# WhatCompressor.net
KiCad netlist of a schematic drawn in EAGLE
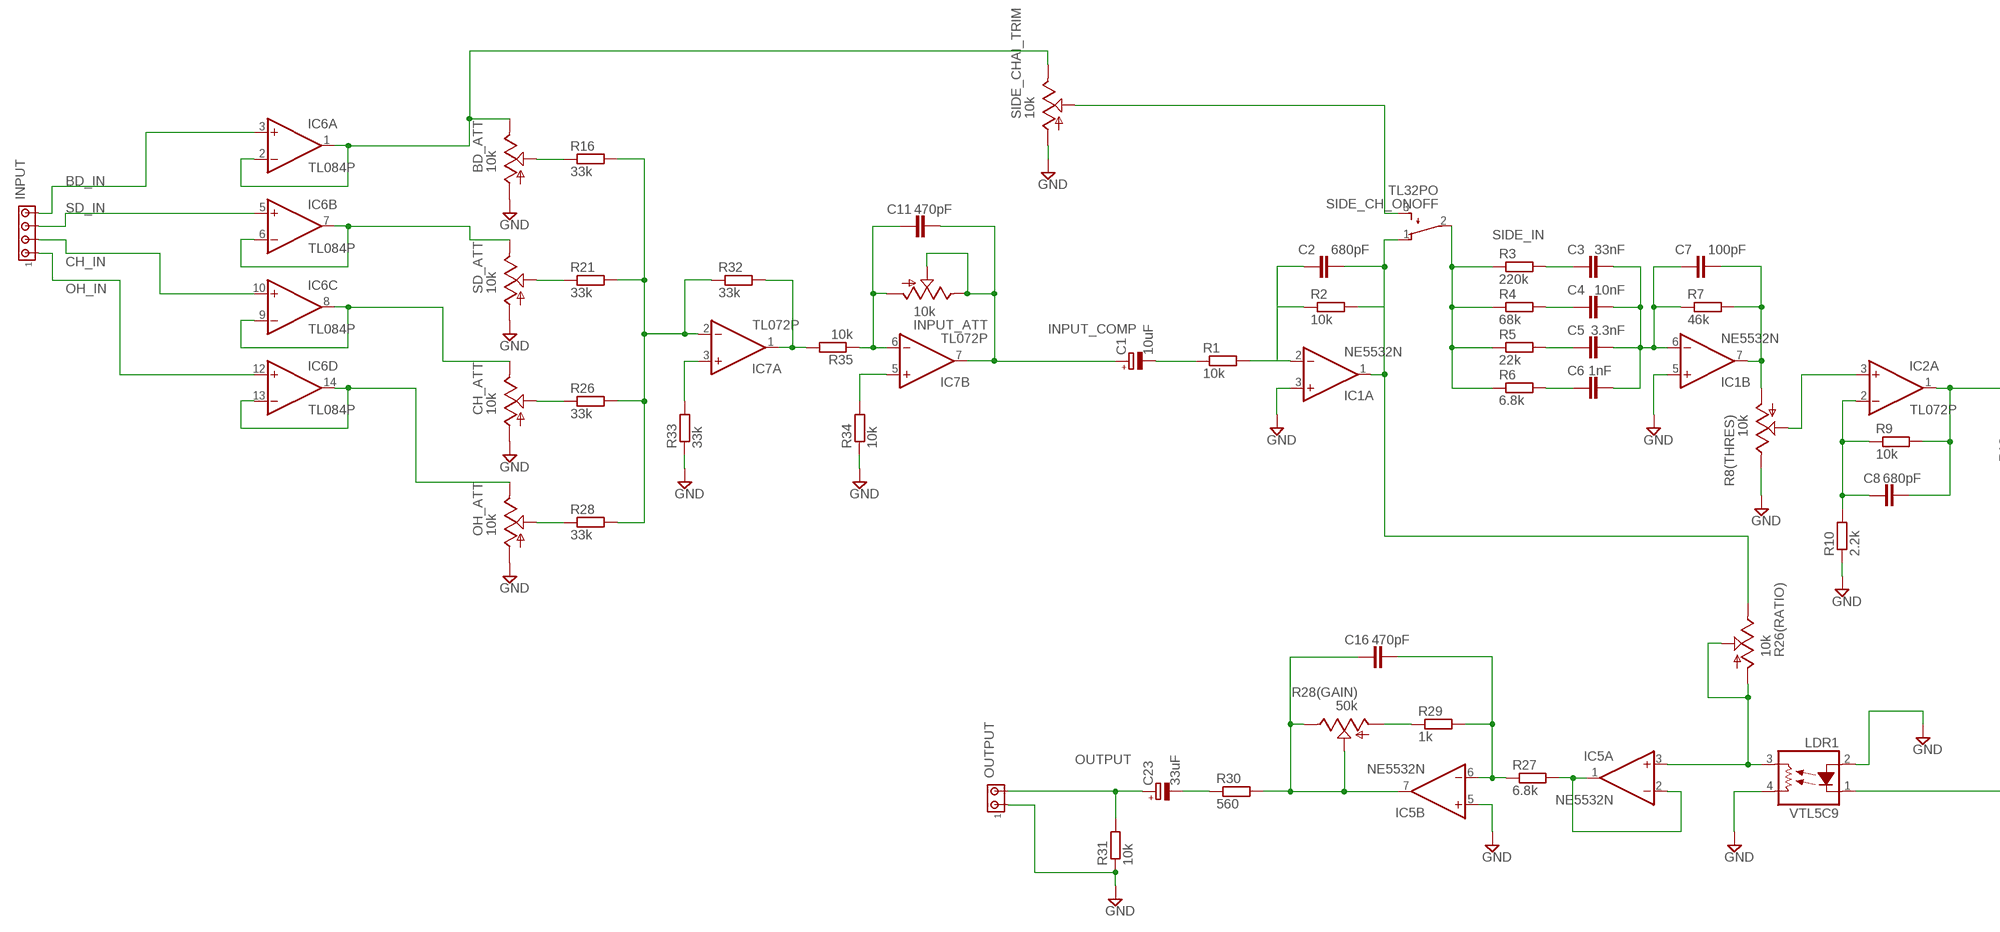
[diagram p0: schematic, sheet 1, part 1 of 2]
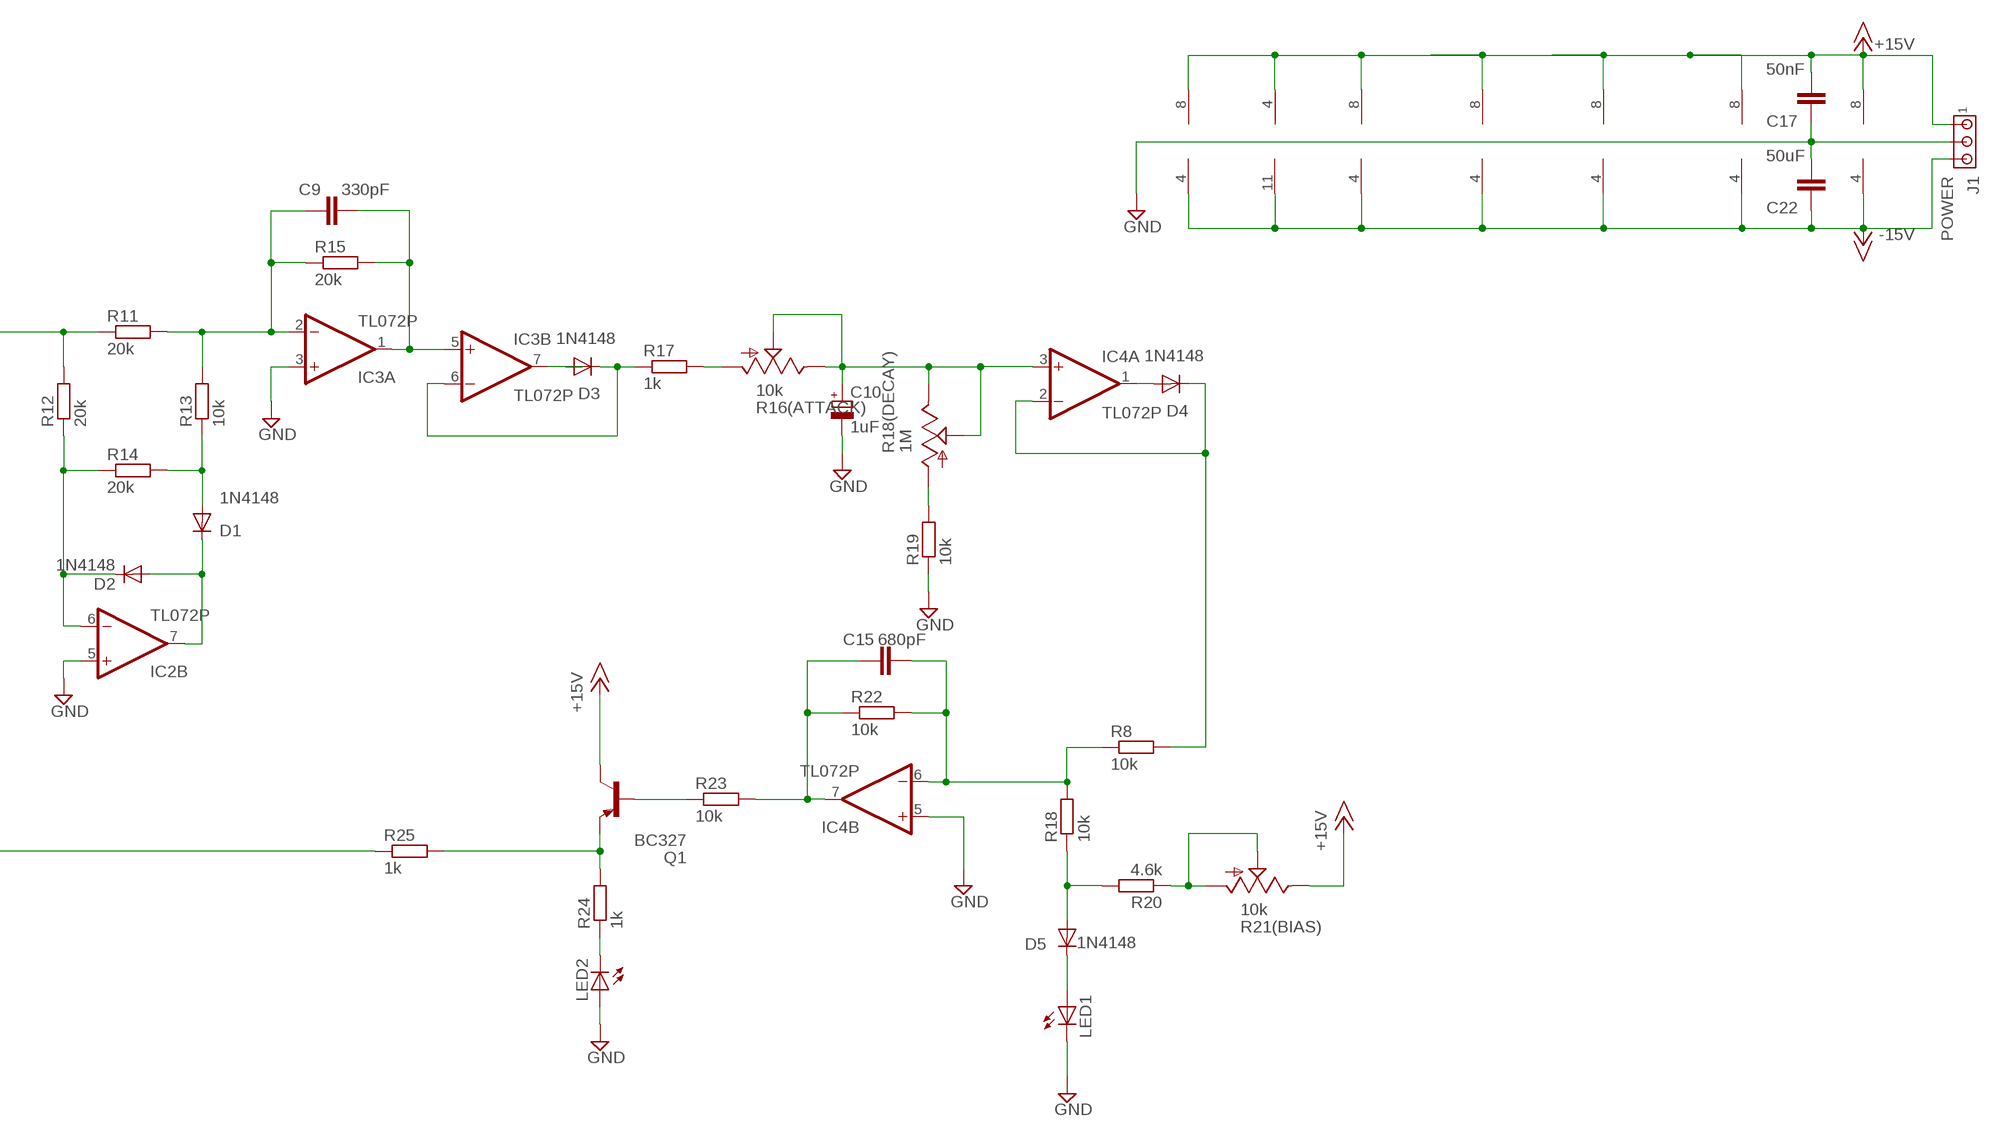
[diagram p1: schematic, sheet 1, part 2 of 2]

(export (version "E")
  (design (tool "Eeschema 10.0.6"))
  (components
    (comp (ref "BD_ATT")
      (value "10k")
      (footprint "eagle-import:B64Y")
      (libsource (lib "eagle-import") (part "TRIM_US-B64Y"))
    )
    (comp (ref "C1")
      (value "10uF")
      (footprint "eagle-import:E2,5-5")
      (fields (field (name "MF") "RUBYCON") (field (name "MPN") "100PK10MEFC5X11"))
      (libsource (lib "eagle-import") (part "CPOL-EUE2.5-5"))
    )
    (comp (ref "C2")
      (value "680pF")
      (footprint "eagle-import:C050-024X044")
      (fields (field (name "MF") "VISHAY BC COMPONENTS") (field (name "MPN") "F681K33Y5RN6UK5R"))
      (libsource (lib "eagle-import") (part "C-EU050-024X044"))
    )
    (comp (ref "C3")
      (value "33nF")
      (footprint "eagle-import:C050-024X044")
      (fields (field (name "MF") "AVX") (field (name "MPN") "SR201C333KAR"))
      (libsource (lib "eagle-import") (part "C-EU050-024X044"))
    )
    (comp (ref "C4")
      (value "10nF")
      (footprint "eagle-import:C050-024X044")
      (fields (field (name "MF") "VISHAY") (field (name "MPN") "K103K15X7RF5TH5V"))
      (libsource (lib "eagle-import") (part "C-EU050-024X044"))
    )
    (comp (ref "C5")
      (value "3.3nF")
      (footprint "eagle-import:C050-024X044")
      (fields (field (name "MF") "MULTICOMP") (field (name "MPN") "MCBU7332K6"))
      (libsource (lib "eagle-import") (part "C-EU050-024X044"))
    )
    (comp (ref "C6")
      (value "1nF")
      (footprint "eagle-import:C050-024X044")
      (fields (field (name "MF") "VISHAY") (field (name "MPN") "K102K15X7RF5TH5V"))
      (libsource (lib "eagle-import") (part "C-EU050-024X044"))
    )
    (comp (ref "C7")
      (value "100pF")
      (footprint "eagle-import:C050-024X044")
      (fields (field (name "MF") "VISHAY BC COMPONENTS") (field (name "MPN") "F101K25Y5RP6UK5R"))
      (libsource (lib "eagle-import") (part "C-EU050-024X044"))
    )
    (comp (ref "C8")
      (value "680pF")
      (footprint "eagle-import:C050-024X044")
      (fields (field (name "MF") "VISHAY BC COMPONENTS") (field (name "MPN") "F681K33Y5RN6UK5R"))
      (libsource (lib "eagle-import") (part "C-EU050-024X044"))
    )
    (comp (ref "C9")
      (value "330pF")
      (footprint "eagle-import:C050-024X044")
      (fields (field (name "MF") "VISHAY BC COMPONENTS") (field (name "MPN") "F331K29Y5RN6UK5R"))
      (libsource (lib "eagle-import") (part "C-EU050-024X044"))
    )
    (comp (ref "C10")
      (value "1uF")
      (footprint "eagle-import:E2,5-5")
      (fields (field (name "MF") "PANASONIC") (field (name "MPN") "ECEA1HKS010"))
      (libsource (lib "eagle-import") (part "CPOL-EUE2.5-5"))
    )
    (comp (ref "C11")
      (value "470pF")
      (footprint "eagle-import:C050-024X044")
      (fields (field (name "MF") "MULTICOMP") (field (name "MPN") "MCBU7332K6"))
      (libsource (lib "eagle-import") (part "C-EU050-024X044"))
    )
    (comp (ref "C15")
      (value "680pF")
      (footprint "eagle-import:C050-024X044")
      (fields (field (name "MF") "VISHAY BC COMPONENTS") (field (name "MPN") "F681K33Y5RN6UK5R"))
      (libsource (lib "eagle-import") (part "C-EU050-024X044"))
    )
    (comp (ref "C16")
      (value "470pF")
      (footprint "eagle-import:C050-024X044")
      (fields (field (name "MF") "MULTICOMP") (field (name "MPN") "MCBU7332K6"))
      (libsource (lib "eagle-import") (part "C-EU050-024X044"))
    )
    (comp (ref "C17")
      (value "50nF")
      (footprint "eagle-import:C050-024X044")
      (fields (field (name "MF") "VISHAY") (field (name "MPN") "K103K15X7RF5TH5V"))
      (libsource (lib "eagle-import") (part "C-EU050-024X044"))
    )
    (comp (ref "C22")
      (value "50uF")
      (footprint "eagle-import:C050-024X044")
      (fields (field (name "MF") "VISHAY") (field (name "MPN") "K103K15X7RF5TH5V"))
      (libsource (lib "eagle-import") (part "C-EU050-024X044"))
    )
    (comp (ref "C23")
      (value "33uF")
      (footprint "eagle-import:E2,5-5")
      (fields (field (name "MF") "RUBYCON") (field (name "MPN") "100PK10MEFC5X11"))
      (libsource (lib "eagle-import") (part "CPOL-EUE2.5-5"))
    )
    (comp (ref "CH_ATT")
      (value "10k")
      (footprint "eagle-import:B64Y")
      (libsource (lib "eagle-import") (part "TRIM_US-B64Y"))
    )
    (comp (ref "D1")
      (value "1N4148")
      (footprint "eagle-import:DO35-7")
      (fields (field (name "MF") "NXP"))
      (libsource (lib "eagle-import") (part "1N4148DO35-7"))
    )
    (comp (ref "D2")
      (value "1N4148")
      (footprint "eagle-import:DO35-7")
      (fields (field (name "MF") "NXP"))
      (libsource (lib "eagle-import") (part "1N4148DO35-7"))
    )
    (comp (ref "D3")
      (value "1N4148")
      (footprint "eagle-import:DO35-7")
      (fields (field (name "MF") "NXP"))
      (libsource (lib "eagle-import") (part "1N4148DO35-7"))
    )
    (comp (ref "D4")
      (value "1N4148")
      (footprint "eagle-import:DO35-7")
      (fields (field (name "MF") "NXP"))
      (libsource (lib "eagle-import") (part "1N4148DO35-7"))
    )
    (comp (ref "D5")
      (value "1N4148")
      (footprint "eagle-import:DO35-7")
      (fields (field (name "MF") "NXP"))
      (libsource (lib "eagle-import") (part "1N4148DO35-7"))
    )
    (comp (ref "IC1")
      (value "NE5532N")
      (footprint "eagle-import:DIL08")
      (fields
        (field (name "MF") "TEXAS INSTRUMENTS")
        (field (name "MPN") "NE5532P")
        (field (name "OC_FARNELL") "1106092")
      )
      (libsource (lib "eagle-import") (part "NE5532N"))
    )
    (comp (ref "IC2")
      (value "TL072P")
      (footprint "eagle-import:DIL08")
      (fields
        (field (name "MF") "TEXAS INSTRUMENTS")
        (field (name "MPN") "TL072IP")
        (field (name "OC_FARNELL") "1459704")
      )
      (libsource (lib "eagle-import") (part "TL072P"))
    )
    (comp (ref "IC3")
      (value "TL072P")
      (footprint "eagle-import:DIL08")
      (fields
        (field (name "MF") "TEXAS INSTRUMENTS")
        (field (name "MPN") "TL072IP")
        (field (name "OC_FARNELL") "1459704")
      )
      (libsource (lib "eagle-import") (part "TL072P"))
    )
    (comp (ref "IC4")
      (value "TL072P")
      (footprint "eagle-import:DIL08")
      (fields
        (field (name "MF") "TEXAS INSTRUMENTS")
        (field (name "MPN") "TL072IP")
        (field (name "OC_FARNELL") "1459704")
      )
      (libsource (lib "eagle-import") (part "TL072P"))
    )
    (comp (ref "IC5")
      (value "NE5532N")
      (footprint "eagle-import:DIL08")
      (libsource (lib "eagle-import") (part "NE5532N"))
    )
    (comp (ref "IC6")
      (value "TL084P")
      (footprint "eagle-import:DIL14")
      (libsource (lib "eagle-import") (part "TL084P"))
    )
    (comp (ref "IC7")
      (value "TL072P")
      (footprint "eagle-import:DIL08")
      (libsource (lib "eagle-import") (part "TL072P"))
    )
    (comp (ref "INPUT")
      (value "MTA04-100")
      (footprint "eagle-import:10X04MTA")
      (libsource (lib "eagle-import") (part "MTA04-100"))
    )
    (comp (ref "INPUT_ATT")
      (value "10k")
      (footprint "eagle-import:B64Y")
      (libsource (lib "eagle-import") (part "TRIM_US-B64Y"))
    )
    (comp (ref "J1")
      (value "POWER")
      (footprint "eagle-import:10X03MTA")
      (libsource (lib "eagle-import") (part "MTA03-100"))
    )
    (comp (ref "LDR1")
      (value "VTL5C9")
      (footprint "eagle-import:VTL5C")
      (fields (field (name "MF") "VACTEC PHOTO"))
      (libsource (lib "eagle-import") (part "VTL5C9"))
    )
    (comp (ref "LED1")
      (value "LED5MM")
      (footprint "eagle-import:LED5MM")
      (libsource (lib "eagle-import") (part "LED5MM"))
    )
    (comp (ref "LED2")
      (value "LED5MM")
      (footprint "eagle-import:LED5MM")
      (libsource (lib "eagle-import") (part "LED5MM"))
    )
    (comp (ref "OH_ATT")
      (value "10k")
      (footprint "eagle-import:B64Y")
      (libsource (lib "eagle-import") (part "TRIM_US-B64Y"))
    )
    (comp (ref "OUTPUT")
      (value "MTA02-100")
      (footprint "eagle-import:10X02MTA")
      (libsource (lib "eagle-import") (part "MTA02-100"))
    )
    (comp (ref "Q1")
      (value "BC327")
      (footprint "eagle-import:TO92-EBC")
      (libsource (lib "eagle-import") (part "BC327"))
    )
    (comp (ref "R1")
      (value "10k")
      (footprint "eagle-import:0204_7")
      (fields (field (name "MF") "MULTICOMP") (field (name "MPN") "MCCFR0W4J0103A50"))
      (libsource (lib "eagle-import") (part "R-EU_0204/7"))
    )
    (comp (ref "R2")
      (value "10k")
      (footprint "eagle-import:0204_7")
      (fields (field (name "MF") "MULTICOMP") (field (name "MPN") "MCCFR0W4J0103A50"))
      (libsource (lib "eagle-import") (part "R-EU_0204/7"))
    )
    (comp (ref "R3")
      (value "220k")
      (footprint "eagle-import:0204_7")
      (fields (field (name "MF") "TE CONNECTIVITY") (field (name "MPN") "CFR16J220K"))
      (libsource (lib "eagle-import") (part "R-EU_0204/7"))
    )
    (comp (ref "R4")
      (value "68k")
      (footprint "eagle-import:0204_7")
      (fields (field (name "MF") "TE CONNECTIVITY") (field (name "MPN") "CFR16J68K"))
      (libsource (lib "eagle-import") (part "R-EU_0204/7"))
    )
    (comp (ref "R5")
      (value "22k")
      (footprint "eagle-import:0204_7")
      (fields (field (name "MF") "TE CONNECTIVITY") (field (name "MPN") "CFR16J22K"))
      (libsource (lib "eagle-import") (part "R-EU_0204/7"))
    )
    (comp (ref "R6")
      (value "6.8k")
      (footprint "eagle-import:0204_7")
      (fields (field (name "MF") "MULTICOMP") (field (name "MPN") "MF25 6K8"))
      (libsource (lib "eagle-import") (part "R-EU_0204/7"))
    )
    (comp (ref "R7")
      (value "46k")
      (footprint "eagle-import:0204_7")
      (fields (field (name "MF") "TE CONNECTIVITY") (field (name "MPN") "CFR16J47K"))
      (libsource (lib "eagle-import") (part "R-EU_0204/7"))
    )
    (comp (ref "R8")
      (value "10k")
      (footprint "eagle-import:0204_7")
      (fields (field (name "MF") "MULTICOMP") (field (name "MPN") "MCF 0.25W 1K"))
      (libsource (lib "eagle-import") (part "R-EU_0204/7"))
    )
    (comp (ref "R8(THRES)")
      (value "10k")
      (footprint "eagle-import:B64Y")
      (libsource (lib "eagle-import") (part "TRIM_US-B64Y"))
    )
    (comp (ref "R9")
      (value "10k")
      (footprint "eagle-import:0204_7")
      (fields (field (name "MF") "MULTICOMP") (field (name "MPN") "MCCFR0W4J0103A50"))
      (libsource (lib "eagle-import") (part "R-EU_0204/7"))
    )
    (comp (ref "R10")
      (value "2.2k")
      (footprint "eagle-import:0204_7")
      (fields (field (name "MF") "MULTICOMP") (field (name "MPN") "MF25 2K2"))
      (libsource (lib "eagle-import") (part "R-EU_0204/7"))
    )
    (comp (ref "R11")
      (value "20k")
      (footprint "eagle-import:0204_7")
      (fields (field (name "MF") "TE CONNECTIVITY") (field (name "MPN") "LR0204F20K"))
      (libsource (lib "eagle-import") (part "R-EU_0204/7"))
    )
    (comp (ref "R12")
      (value "20k")
      (footprint "eagle-import:0204_7")
      (fields (field (name "MF") "TE CONNECTIVITY") (field (name "MPN") "LR0204F20K"))
      (libsource (lib "eagle-import") (part "R-EU_0204/7"))
    )
    (comp (ref "R13")
      (value "10k")
      (footprint "eagle-import:0204_7")
      (fields (field (name "MF") "MULTICOMP") (field (name "MPN") "MCCFR0W4J0103A50"))
      (libsource (lib "eagle-import") (part "R-EU_0204/7"))
    )
    (comp (ref "R14")
      (value "20k")
      (footprint "eagle-import:0204_7")
      (fields (field (name "MF") "TE CONNECTIVITY") (field (name "MPN") "LR0204F20K"))
      (libsource (lib "eagle-import") (part "R-EU_0204/7"))
    )
    (comp (ref "R15")
      (value "20k")
      (footprint "eagle-import:0204_7")
      (fields (field (name "MF") "TE CONNECTIVITY") (field (name "MPN") "LR0204F20K"))
      (libsource (lib "eagle-import") (part "R-EU_0204/7"))
    )
    (comp (ref "R16")
      (value "33k")
      (footprint "eagle-import:0204_7")
      (fields (field (name "MF") "TE CONNECTIVITY") (field (name "MPN") "CFR16J220K"))
      (libsource (lib "eagle-import") (part "R-EU_0204/7"))
    )
    (comp (ref "R16(ATTACK)")
      (value "10k")
      (footprint "eagle-import:B64Y")
      (libsource (lib "eagle-import") (part "TRIM_US-B64Y"))
    )
    (comp (ref "R17")
      (value "1k")
      (footprint "eagle-import:0204_7")
      (fields (field (name "MF") "MULTICOMP") (field (name "MPN") "MCF 0.25W 1K"))
      (libsource (lib "eagle-import") (part "R-EU_0204/7"))
    )
    (comp (ref "R18")
      (value "10k")
      (footprint "eagle-import:0204_7")
      (fields (field (name "MF") "MULTICOMP") (field (name "MPN") "MCF 0.25W 1K"))
      (libsource (lib "eagle-import") (part "R-EU_0204/7"))
    )
    (comp (ref "R18(DECAY)")
      (value "1M")
      (footprint "eagle-import:B64Y")
      (libsource (lib "eagle-import") (part "TRIM_US-B64Y"))
    )
    (comp (ref "R19")
      (value "10k")
      (footprint "eagle-import:0204_7")
      (fields (field (name "MF") "MULTICOMP") (field (name "MPN") "MCCFR0W4J0103A50"))
      (libsource (lib "eagle-import") (part "R-EU_0204/7"))
    )
    (comp (ref "R20")
      (value "4.6k")
      (footprint "eagle-import:0204_7")
      (fields (field (name "MF") "MULTICOMP") (field (name "MPN") "MCF 0.25W 1K"))
      (libsource (lib "eagle-import") (part "R-EU_0204/7"))
    )
    (comp (ref "R21")
      (value "33k")
      (footprint "eagle-import:0204_7")
      (fields (field (name "MF") "TE CONNECTIVITY") (field (name "MPN") "CFR16J220K"))
      (libsource (lib "eagle-import") (part "R-EU_0204/7"))
    )
    (comp (ref "R21(BIAS)")
      (value "10k")
      (footprint "eagle-import:B64Y")
      (libsource (lib "eagle-import") (part "TRIM_US-B64Y"))
    )
    (comp (ref "R22")
      (value "10k")
      (footprint "eagle-import:0204_7")
      (fields (field (name "MF") "TE CONNECTIVITY") (field (name "MPN") "LR0204F20K"))
      (libsource (lib "eagle-import") (part "R-EU_0204/7"))
    )
    (comp (ref "R23")
      (value "10k")
      (footprint "eagle-import:0204_7")
      (fields (field (name "MF") "TE CONNECTIVITY") (field (name "MPN") "LR0204F20K"))
      (libsource (lib "eagle-import") (part "R-EU_0204/7"))
    )
    (comp (ref "R24")
      (value "1k")
      (footprint "eagle-import:0204_7")
      (fields (field (name "MF") "TE CONNECTIVITY") (field (name "MPN") "LR0204F20K"))
      (libsource (lib "eagle-import") (part "R-EU_0204/7"))
    )
    (comp (ref "R25")
      (value "1k")
      (footprint "eagle-import:0204_7")
      (fields (field (name "MF") "TE CONNECTIVITY") (field (name "MPN") "LR0204F20K"))
      (libsource (lib "eagle-import") (part "R-EU_0204/7"))
    )
    (comp (ref "R26")
      (value "33k")
      (footprint "eagle-import:0204_7")
      (fields (field (name "MF") "TE CONNECTIVITY") (field (name "MPN") "CFR16J220K"))
      (libsource (lib "eagle-import") (part "R-EU_0204/7"))
    )
    (comp (ref "R26(RATIO)")
      (value "10k")
      (footprint "eagle-import:B64Y")
      (libsource (lib "eagle-import") (part "TRIM_US-B64Y"))
    )
    (comp (ref "R27")
      (value "6.8k")
      (footprint "eagle-import:0204_7")
      (fields (field (name "MF") "MULTICOMP") (field (name "MPN") "MF25 6K8"))
      (libsource (lib "eagle-import") (part "R-EU_0204/7"))
    )
    (comp (ref "R28")
      (value "33k")
      (footprint "eagle-import:0204_7")
      (fields (field (name "MF") "TE CONNECTIVITY") (field (name "MPN") "CFR16J220K"))
      (libsource (lib "eagle-import") (part "R-EU_0204/7"))
    )
    (comp (ref "R28(GAIN)")
      (value "50k")
      (footprint "eagle-import:B64Y")
      (libsource (lib "eagle-import") (part "TRIM_US-B64Y"))
    )
    (comp (ref "R29")
      (value "1k")
      (footprint "eagle-import:0204_7")
      (fields (field (name "MF") "MULTICOMP") (field (name "MPN") "MF25 6K8"))
      (libsource (lib "eagle-import") (part "R-EU_0204/7"))
    )
    (comp (ref "R30")
      (value "560")
      (footprint "eagle-import:0204_7")
      (fields (field (name "MF") "MULTICOMP") (field (name "MPN") "MCCFR0W4J0103A50"))
      (libsource (lib "eagle-import") (part "R-EU_0204/7"))
    )
    (comp (ref "R31")
      (value "10k")
      (footprint "eagle-import:0204_7")
      (fields (field (name "MF") "MULTICOMP") (field (name "MPN") "MCCFR0W4J0103A50"))
      (libsource (lib "eagle-import") (part "R-EU_0204/7"))
    )
    (comp (ref "R32")
      (value "33k")
      (footprint "eagle-import:0204_7")
      (fields (field (name "MF") "TE CONNECTIVITY") (field (name "MPN") "CFR16J220K"))
      (libsource (lib "eagle-import") (part "R-EU_0204/7"))
    )
    (comp (ref "R33")
      (value "33k")
      (footprint "eagle-import:0204_7")
      (fields (field (name "MF") "TE CONNECTIVITY") (field (name "MPN") "CFR16J220K"))
      (libsource (lib "eagle-import") (part "R-EU_0204/7"))
    )
    (comp (ref "R34")
      (value "10k")
      (footprint "eagle-import:0204_7")
      (fields (field (name "MF") "TE CONNECTIVITY") (field (name "MPN") "CFR16J220K"))
      (libsource (lib "eagle-import") (part "R-EU_0204/7"))
    )
    (comp (ref "R35")
      (value "10k")
      (footprint "eagle-import:0204_7")
      (fields (field (name "MF") "TE CONNECTIVITY") (field (name "MPN") "CFR16J220K"))
      (libsource (lib "eagle-import") (part "R-EU_0204/7"))
    )
    (comp (ref "SD_ATT")
      (value "10k")
      (footprint "eagle-import:B64Y")
      (libsource (lib "eagle-import") (part "TRIM_US-B64Y"))
    )
    (comp (ref "SIDE_CHAI_TRIM")
      (value "10k")
      (footprint "eagle-import:B64Y")
      (libsource (lib "eagle-import") (part "TRIM_US-B64Y"))
    )
    (comp (ref "SIDE_CH_ONOFF")
      (value "TL32PO")
      (footprint "eagle-import:TL3XPO")
      (libsource (lib "eagle-import") (part "TL32PO"))
    )
  )
  (nets
    (net (code "1") (name "+15V") (class "Default")
      (node (ref "C17") (pin "2") (pinfunction "2_2") (pintype "passive"))
      (node (ref "IC1") (pin "8") (pinfunction "V+_8") (pintype "power_in"))
      (node (ref "IC2") (pin "8") (pinfunction "V+_8") (pintype "power_in"))
      (node (ref "IC3") (pin "8") (pinfunction "V+_8") (pintype "power_in"))
      (node (ref "IC4") (pin "8") (pinfunction "V+_8") (pintype "power_in"))
      (node (ref "IC5") (pin "8") (pinfunction "V+_8") (pintype "power_in"))
      (node (ref "IC6") (pin "4") (pinfunction "V+_4") (pintype "power_in"))
      (node (ref "IC7") (pin "8") (pinfunction "V+_8") (pintype "power_in"))
      (node (ref "J1") (pin "1") (pinfunction "1_1") (pintype "passive"))
      (node (ref "Q1") (pin "C") (pinfunction "C_C") (pintype "passive"))
      (node (ref "R21(BIAS)") (pin "E") (pinfunction "E_E") (pintype "passive"))
    )
    (net (code "2") (name "-15V") (class "Default")
      (node (ref "C22") (pin "1") (pinfunction "1_1") (pintype "passive"))
      (node (ref "IC1") (pin "4") (pinfunction "V-_4") (pintype "power_in"))
      (node (ref "IC2") (pin "4") (pinfunction "V-_4") (pintype "power_in"))
      (node (ref "IC3") (pin "4") (pinfunction "V-_4") (pintype "power_in"))
      (node (ref "IC4") (pin "4") (pinfunction "V-_4") (pintype "power_in"))
      (node (ref "IC5") (pin "4") (pinfunction "V-_4") (pintype "power_in"))
      (node (ref "IC6") (pin "11") (pinfunction "V-_11") (pintype "power_in"))
      (node (ref "IC7") (pin "4") (pinfunction "V-_4") (pintype "power_in"))
      (node (ref "J1") (pin "3") (pinfunction "3_3") (pintype "passive"))
    )
    (net (code "3") (name "/BD_IN") (class "Default")
      (node (ref "IC6") (pin "3") (pinfunction "+IN_3") (pintype "input"))
      (node (ref "INPUT") (pin "4") (pinfunction "4_4") (pintype "passive"))
    )
    (net (code "4") (name "/CH_IN") (class "Default")
      (node (ref "IC6") (pin "10") (pinfunction "+IN_10") (pintype "input"))
      (node (ref "INPUT") (pin "2") (pinfunction "2_2") (pintype "passive"))
    )
    (net (code "5") (name "/INPUT_COMP") (class "Default")
      (node (ref "C1") (pin "+") (pinfunction "+_+") (pintype "passive"))
      (node (ref "C11") (pin "2") (pinfunction "2_2") (pintype "passive"))
      (node (ref "IC7") (pin "7") (pinfunction "OUT_7") (pintype "output"))
      (node (ref "INPUT_ATT") (pin "E") (pinfunction "E_E") (pintype "passive"))
      (node (ref "INPUT_ATT") (pin "S") (pinfunction "S_S") (pintype "passive"))
    )
    (net (code "6") (name "/OH_IN") (class "Default")
      (node (ref "IC6") (pin "12") (pinfunction "+IN_12") (pintype "input"))
      (node (ref "INPUT") (pin "1") (pinfunction "1_1") (pintype "passive"))
    )
    (net (code "7") (name "/OUTPUT") (class "Default")
      (node (ref "C23") (pin "+") (pinfunction "+_+") (pintype "passive"))
      (node (ref "OUTPUT") (pin "2") (pinfunction "2_2") (pintype "passive"))
      (node (ref "R31") (pin "2") (pinfunction "2_2") (pintype "passive"))
    )
    (net (code "8") (name "/SD_IN") (class "Default")
      (node (ref "IC6") (pin "5") (pinfunction "+IN_5") (pintype "input"))
      (node (ref "INPUT") (pin "3") (pinfunction "3_3") (pintype "passive"))
    )
    (net (code "9") (name "/SIDE_IN") (class "Default")
      (node (ref "R3") (pin "1") (pinfunction "1_1") (pintype "passive"))
      (node (ref "R4") (pin "1") (pinfunction "1_1") (pintype "passive"))
      (node (ref "R5") (pin "1") (pinfunction "1_1") (pintype "passive"))
      (node (ref "R6") (pin "1") (pinfunction "1_1") (pintype "passive"))
      (node (ref "SIDE_CH_ONOFF") (pin "2") (pinfunction "P_2") (pintype "passive"))
    )
    (net (code "10") (name "GND") (class "Default")
      (node (ref "BD_ATT") (pin "A") (pinfunction "A_A") (pintype "passive"))
      (node (ref "C10") (pin "-") (pinfunction "-_-") (pintype "passive"))
      (node (ref "C17") (pin "1") (pinfunction "1_1") (pintype "passive"))
      (node (ref "C22") (pin "2") (pinfunction "2_2") (pintype "passive"))
      (node (ref "CH_ATT") (pin "A") (pinfunction "A_A") (pintype "passive"))
      (node (ref "IC1") (pin "3") (pinfunction "+IN_3") (pintype "input"))
      (node (ref "IC1") (pin "5") (pinfunction "+IN_5") (pintype "input"))
      (node (ref "IC2") (pin "5") (pinfunction "+IN_5") (pintype "input"))
      (node (ref "IC3") (pin "3") (pinfunction "+IN_3") (pintype "input"))
      (node (ref "IC4") (pin "5") (pinfunction "+IN_5") (pintype "input"))
      (node (ref "IC5") (pin "5") (pinfunction "+IN_5") (pintype "input"))
      (node (ref "J1") (pin "2") (pinfunction "2_2") (pintype "passive"))
      (node (ref "LDR1") (pin "2") (pinfunction "A_2") (pintype "passive"))
      (node (ref "LDR1") (pin "4") (pinfunction "L2_4") (pintype "passive"))
      (node (ref "LED1") (pin "K") (pinfunction "C_K") (pintype "passive"))
      (node (ref "LED2") (pin "A") (pinfunction "A_A") (pintype "passive"))
      (node (ref "OH_ATT") (pin "A") (pinfunction "A_A") (pintype "passive"))
      (node (ref "OUTPUT") (pin "1") (pinfunction "1_1") (pintype "passive"))
      (node (ref "R10") (pin "1") (pinfunction "1_1") (pintype "passive"))
      (node (ref "R19") (pin "1") (pinfunction "1_1") (pintype "passive"))
      (node (ref "R31") (pin "1") (pinfunction "1_1") (pintype "passive"))
      (node (ref "R33") (pin "1") (pinfunction "1_1") (pintype "passive"))
      (node (ref "R34") (pin "1") (pinfunction "1_1") (pintype "passive"))
      (node (ref "R8(THRES)") (pin "E") (pinfunction "E_E") (pintype "passive"))
      (node (ref "SD_ATT") (pin "A") (pinfunction "A_A") (pintype "passive"))
      (node (ref "SIDE_CHAI_TRIM") (pin "A") (pinfunction "A_A") (pintype "passive"))
    )
    (net (code "11") (name "Net-(BD_ATT-PadS)") (class "Default")
      (node (ref "BD_ATT") (pin "S") (pinfunction "S_S") (pintype "passive"))
      (node (ref "R16") (pin "1") (pinfunction "1_1") (pintype "passive"))
    )
    (net (code "12") (name "Net-(C1-Pad-)") (class "Default")
      (node (ref "C1") (pin "-") (pinfunction "-_-") (pintype "passive"))
      (node (ref "R1") (pin "1") (pinfunction "1_1") (pintype "passive"))
    )
    (net (code "13") (name "Net-(C3-Pad1)") (class "Default")
      (node (ref "C3") (pin "1") (pinfunction "1_1") (pintype "passive"))
      (node (ref "R3") (pin "2") (pinfunction "2_2") (pintype "passive"))
    )
    (net (code "14") (name "Net-(C4-Pad1)") (class "Default")
      (node (ref "C4") (pin "1") (pinfunction "1_1") (pintype "passive"))
      (node (ref "R4") (pin "2") (pinfunction "2_2") (pintype "passive"))
    )
    (net (code "15") (name "Net-(C5-Pad1)") (class "Default")
      (node (ref "C5") (pin "1") (pinfunction "1_1") (pintype "passive"))
      (node (ref "R5") (pin "2") (pinfunction "2_2") (pintype "passive"))
    )
    (net (code "16") (name "Net-(C6-Pad1)") (class "Default")
      (node (ref "C6") (pin "1") (pinfunction "1_1") (pintype "passive"))
      (node (ref "R6") (pin "2") (pinfunction "2_2") (pintype "passive"))
    )
    (net (code "17") (name "Net-(C23-Pad-)") (class "Default")
      (node (ref "C23") (pin "-") (pinfunction "-_-") (pintype "passive"))
      (node (ref "R30") (pin "1") (pinfunction "1_1") (pintype "passive"))
    )
    (net (code "18") (name "Net-(CH_ATT-PadS)") (class "Default")
      (node (ref "CH_ATT") (pin "S") (pinfunction "S_S") (pintype "passive"))
      (node (ref "R26") (pin "1") (pinfunction "1_1") (pintype "passive"))
    )
    (net (code "19") (name "Net-(D1-PadA)") (class "Default")
      (node (ref "D1") (pin "A") (pinfunction "A_A") (pintype "passive"))
      (node (ref "R13") (pin "1") (pinfunction "1_1") (pintype "passive"))
      (node (ref "R14") (pin "2") (pinfunction "2_2") (pintype "passive"))
    )
    (net (code "20") (name "Net-(D5-PadA)") (class "Default")
      (node (ref "D5") (pin "A") (pinfunction "A_A") (pintype "passive"))
      (node (ref "R18") (pin "1") (pinfunction "1_1") (pintype "passive"))
      (node (ref "R20") (pin "2") (pinfunction "2_2") (pintype "passive"))
    )
    (net (code "21") (name "Net-(D5-PadC)") (class "Default")
      (node (ref "D5") (pin "C") (pinfunction "C_C") (pintype "passive"))
      (node (ref "LED1") (pin "A") (pinfunction "A_A") (pintype "passive"))
    )
    (net (code "22") (name "Net-(IC1A--IN)") (class "Default")
      (node (ref "C2") (pin "1") (pinfunction "1_1") (pintype "passive"))
      (node (ref "IC1") (pin "2") (pinfunction "-IN_2") (pintype "input"))
      (node (ref "R1") (pin "2") (pinfunction "2_2") (pintype "passive"))
      (node (ref "R2") (pin "1") (pinfunction "1_1") (pintype "passive"))
    )
    (net (code "23") (name "Net-(IC1A-OUT)") (class "Default")
      (node (ref "C2") (pin "2") (pinfunction "2_2") (pintype "passive"))
      (node (ref "IC1") (pin "1") (pinfunction "OUT_1") (pintype "output"))
      (node (ref "R2") (pin "2") (pinfunction "2_2") (pintype "passive"))
      (node (ref "R26(RATIO)") (pin "E") (pinfunction "E_E") (pintype "passive"))
      (node (ref "SIDE_CH_ONOFF") (pin "1") (pinfunction "O_1") (pintype "passive"))
    )
    (net (code "24") (name "Net-(IC1B--IN)") (class "Default")
      (node (ref "C3") (pin "2") (pinfunction "2_2") (pintype "passive"))
      (node (ref "C4") (pin "2") (pinfunction "2_2") (pintype "passive"))
      (node (ref "C5") (pin "2") (pinfunction "2_2") (pintype "passive"))
      (node (ref "C6") (pin "2") (pinfunction "2_2") (pintype "passive"))
      (node (ref "C7") (pin "1") (pinfunction "1_1") (pintype "passive"))
      (node (ref "IC1") (pin "6") (pinfunction "-IN_6") (pintype "input"))
      (node (ref "R7") (pin "1") (pinfunction "1_1") (pintype "passive"))
    )
    (net (code "25") (name "Net-(IC1B-OUT)") (class "Default")
      (node (ref "C7") (pin "2") (pinfunction "2_2") (pintype "passive"))
      (node (ref "IC1") (pin "7") (pinfunction "OUT_7") (pintype "output"))
      (node (ref "R7") (pin "2") (pinfunction "2_2") (pintype "passive"))
      (node (ref "R8(THRES)") (pin "A") (pinfunction "A_A") (pintype "passive"))
    )
    (net (code "26") (name "Net-(IC2A-+IN)") (class "Default")
      (node (ref "IC2") (pin "3") (pinfunction "+IN_3") (pintype "input"))
      (node (ref "R8(THRES)") (pin "S") (pinfunction "S_S") (pintype "passive"))
    )
    (net (code "27") (name "Net-(IC2A--IN)") (class "Default")
      (node (ref "C8") (pin "1") (pinfunction "1_1") (pintype "passive"))
      (node (ref "IC2") (pin "2") (pinfunction "-IN_2") (pintype "input"))
      (node (ref "R10") (pin "2") (pinfunction "2_2") (pintype "passive"))
      (node (ref "R9") (pin "1") (pinfunction "1_1") (pintype "passive"))
    )
    (net (code "28") (name "Net-(IC2A-OUT)") (class "Default")
      (node (ref "C8") (pin "2") (pinfunction "2_2") (pintype "passive"))
      (node (ref "IC2") (pin "1") (pinfunction "OUT_1") (pintype "output"))
      (node (ref "R11") (pin "1") (pinfunction "1_1") (pintype "passive"))
      (node (ref "R12") (pin "2") (pinfunction "2_2") (pintype "passive"))
      (node (ref "R9") (pin "2") (pinfunction "2_2") (pintype "passive"))
    )
    (net (code "29") (name "Net-(IC2B--IN)") (class "Default")
      (node (ref "D2") (pin "C") (pinfunction "C_C") (pintype "passive"))
      (node (ref "IC2") (pin "6") (pinfunction "-IN_6") (pintype "input"))
      (node (ref "R12") (pin "1") (pinfunction "1_1") (pintype "passive"))
      (node (ref "R14") (pin "1") (pinfunction "1_1") (pintype "passive"))
    )
    (net (code "30") (name "Net-(IC2B-OUT)") (class "Default")
      (node (ref "D1") (pin "C") (pinfunction "C_C") (pintype "passive"))
      (node (ref "D2") (pin "A") (pinfunction "A_A") (pintype "passive"))
      (node (ref "IC2") (pin "7") (pinfunction "OUT_7") (pintype "output"))
    )
    (net (code "31") (name "Net-(IC3A--IN)") (class "Default")
      (node (ref "C9") (pin "1") (pinfunction "1_1") (pintype "passive"))
      (node (ref "IC3") (pin "2") (pinfunction "-IN_2") (pintype "input"))
      (node (ref "R11") (pin "2") (pinfunction "2_2") (pintype "passive"))
      (node (ref "R13") (pin "2") (pinfunction "2_2") (pintype "passive"))
      (node (ref "R15") (pin "1") (pinfunction "1_1") (pintype "passive"))
    )
    (net (code "32") (name "Net-(IC3A-OUT)") (class "Default")
      (node (ref "C9") (pin "2") (pinfunction "2_2") (pintype "passive"))
      (node (ref "IC3") (pin "1") (pinfunction "OUT_1") (pintype "output"))
      (node (ref "IC3") (pin "5") (pinfunction "+IN_5") (pintype "input"))
      (node (ref "R15") (pin "2") (pinfunction "2_2") (pintype "passive"))
    )
    (net (code "33") (name "Net-(IC3B--IN)") (class "Default")
      (node (ref "D3") (pin "C") (pinfunction "C_C") (pintype "passive"))
      (node (ref "IC3") (pin "6") (pinfunction "-IN_6") (pintype "input"))
      (node (ref "R17") (pin "1") (pinfunction "1_1") (pintype "passive"))
    )
    (net (code "34") (name "Net-(IC3B-OUT)") (class "Default")
      (node (ref "D3") (pin "A") (pinfunction "A_A") (pintype "passive"))
      (node (ref "IC3") (pin "7") (pinfunction "OUT_7") (pintype "output"))
    )
    (net (code "35") (name "Net-(IC4A-+IN)") (class "Default")
      (node (ref "C10") (pin "+") (pinfunction "+_+") (pintype "passive"))
      (node (ref "IC4") (pin "3") (pinfunction "+IN_3") (pintype "input"))
      (node (ref "R16(ATTACK)") (pin "E") (pinfunction "E_E") (pintype "passive"))
      (node (ref "R16(ATTACK)") (pin "S") (pinfunction "S_S") (pintype "passive"))
      (node (ref "R18(DECAY)") (pin "E") (pinfunction "E_E") (pintype "passive"))
      (node (ref "R18(DECAY)") (pin "S") (pinfunction "S_S") (pintype "passive"))
    )
    (net (code "36") (name "Net-(IC4A--IN)") (class "Default")
      (node (ref "D4") (pin "C") (pinfunction "C_C") (pintype "passive"))
      (node (ref "IC4") (pin "2") (pinfunction "-IN_2") (pintype "input"))
      (node (ref "R8") (pin "2") (pinfunction "2_2") (pintype "passive"))
    )
    (net (code "37") (name "Net-(IC4A-OUT)") (class "Default")
      (node (ref "D4") (pin "A") (pinfunction "A_A") (pintype "passive"))
      (node (ref "IC4") (pin "1") (pinfunction "OUT_1") (pintype "output"))
    )
    (net (code "38") (name "Net-(IC4B--IN)") (class "Default")
      (node (ref "C15") (pin "2") (pinfunction "2_2") (pintype "passive"))
      (node (ref "IC4") (pin "6") (pinfunction "-IN_6") (pintype "input"))
      (node (ref "R18") (pin "2") (pinfunction "2_2") (pintype "passive"))
      (node (ref "R22") (pin "2") (pinfunction "2_2") (pintype "passive"))
      (node (ref "R8") (pin "1") (pinfunction "1_1") (pintype "passive"))
    )
    (net (code "39") (name "Net-(IC4B-OUT)") (class "Default")
      (node (ref "C15") (pin "1") (pinfunction "1_1") (pintype "passive"))
      (node (ref "IC4") (pin "7") (pinfunction "OUT_7") (pintype "output"))
      (node (ref "R22") (pin "1") (pinfunction "1_1") (pintype "passive"))
      (node (ref "R23") (pin "2") (pinfunction "2_2") (pintype "passive"))
    )
    (net (code "40") (name "Net-(IC5A-+IN)") (class "Default")
      (node (ref "IC5") (pin "3") (pinfunction "+IN_3") (pintype "input"))
      (node (ref "LDR1") (pin "3") (pinfunction "L1_3") (pintype "passive"))
      (node (ref "R26(RATIO)") (pin "A") (pinfunction "A_A") (pintype "passive"))
      (node (ref "R26(RATIO)") (pin "S") (pinfunction "S_S") (pintype "passive"))
    )
    (net (code "41") (name "Net-(IC5A--IN)") (class "Default")
      (node (ref "IC5") (pin "1") (pinfunction "OUT_1") (pintype "output"))
      (node (ref "IC5") (pin "2") (pinfunction "-IN_2") (pintype "input"))
      (node (ref "R27") (pin "2") (pinfunction "2_2") (pintype "passive"))
    )
    (net (code "42") (name "Net-(IC5B--IN)") (class "Default")
      (node (ref "C16") (pin "2") (pinfunction "2_2") (pintype "passive"))
      (node (ref "IC5") (pin "6") (pinfunction "-IN_6") (pintype "input"))
      (node (ref "R27") (pin "1") (pinfunction "1_1") (pintype "passive"))
      (node (ref "R29") (pin "2") (pinfunction "2_2") (pintype "passive"))
    )
    (net (code "43") (name "Net-(IC5B-OUT)") (class "Default")
      (node (ref "C16") (pin "1") (pinfunction "1_1") (pintype "passive"))
      (node (ref "IC5") (pin "7") (pinfunction "OUT_7") (pintype "output"))
      (node (ref "R28(GAIN)") (pin "E") (pinfunction "E_E") (pintype "passive"))
      (node (ref "R28(GAIN)") (pin "S") (pinfunction "S_S") (pintype "passive"))
      (node (ref "R30") (pin "2") (pinfunction "2_2") (pintype "passive"))
    )
    (net (code "44") (name "Net-(IC6A--IN)") (class "Default")
      (node (ref "BD_ATT") (pin "E") (pinfunction "E_E") (pintype "passive"))
      (node (ref "IC6") (pin "1") (pinfunction "OUT_1") (pintype "output"))
      (node (ref "IC6") (pin "2") (pinfunction "-IN_2") (pintype "input"))
      (node (ref "SIDE_CHAI_TRIM") (pin "E") (pinfunction "E_E") (pintype "passive"))
    )
    (net (code "45") (name "Net-(IC6B--IN)") (class "Default")
      (node (ref "IC6") (pin "6") (pinfunction "-IN_6") (pintype "input"))
      (node (ref "IC6") (pin "7") (pinfunction "OUT_7") (pintype "output"))
      (node (ref "SD_ATT") (pin "E") (pinfunction "E_E") (pintype "passive"))
    )
    (net (code "46") (name "Net-(IC6C--IN)") (class "Default")
      (node (ref "CH_ATT") (pin "E") (pinfunction "E_E") (pintype "passive"))
      (node (ref "IC6") (pin "8") (pinfunction "OUT_8") (pintype "output"))
      (node (ref "IC6") (pin "9") (pinfunction "-IN_9") (pintype "input"))
    )
    (net (code "47") (name "Net-(IC6D--IN)") (class "Default")
      (node (ref "IC6") (pin "13") (pinfunction "-IN_13") (pintype "input"))
      (node (ref "IC6") (pin "14") (pinfunction "OUT_14") (pintype "output"))
      (node (ref "OH_ATT") (pin "E") (pinfunction "E_E") (pintype "passive"))
    )
    (net (code "48") (name "Net-(IC7A-+IN)") (class "Default")
      (node (ref "IC7") (pin "3") (pinfunction "+IN_3") (pintype "input"))
      (node (ref "R33") (pin "2") (pinfunction "2_2") (pintype "passive"))
    )
    (net (code "49") (name "Net-(IC7A--IN)") (class "Default")
      (node (ref "IC7") (pin "2") (pinfunction "-IN_2") (pintype "input"))
      (node (ref "R16") (pin "2") (pinfunction "2_2") (pintype "passive"))
      (node (ref "R21") (pin "2") (pinfunction "2_2") (pintype "passive"))
      (node (ref "R26") (pin "2") (pinfunction "2_2") (pintype "passive"))
      (node (ref "R28") (pin "2") (pinfunction "2_2") (pintype "passive"))
      (node (ref "R32") (pin "1") (pinfunction "1_1") (pintype "passive"))
    )
    (net (code "50") (name "Net-(IC7A-OUT)") (class "Default")
      (node (ref "IC7") (pin "1") (pinfunction "OUT_1") (pintype "output"))
      (node (ref "R32") (pin "2") (pinfunction "2_2") (pintype "passive"))
      (node (ref "R35") (pin "2") (pinfunction "2_2") (pintype "passive"))
    )
    (net (code "51") (name "Net-(IC7B-+IN)") (class "Default")
      (node (ref "IC7") (pin "5") (pinfunction "+IN_5") (pintype "input"))
      (node (ref "R34") (pin "2") (pinfunction "2_2") (pintype "passive"))
    )
    (net (code "52") (name "Net-(IC7B--IN)") (class "Default")
      (node (ref "C11") (pin "1") (pinfunction "1_1") (pintype "passive"))
      (node (ref "IC7") (pin "6") (pinfunction "-IN_6") (pintype "input"))
      (node (ref "INPUT_ATT") (pin "A") (pinfunction "A_A") (pintype "passive"))
      (node (ref "R35") (pin "1") (pinfunction "1_1") (pintype "passive"))
    )
    (net (code "53") (name "Net-(LDR1-C)") (class "Default")
      (node (ref "LDR1") (pin "1") (pinfunction "C_1") (pintype "passive"))
      (node (ref "R25") (pin "1") (pinfunction "1_1") (pintype "passive"))
    )
    (net (code "54") (name "Net-(LED2-C)") (class "Default")
      (node (ref "LED2") (pin "K") (pinfunction "C_K") (pintype "passive"))
      (node (ref "R24") (pin "1") (pinfunction "1_1") (pintype "passive"))
    )
    (net (code "55") (name "Net-(OH_ATT-PadS)") (class "Default")
      (node (ref "OH_ATT") (pin "S") (pinfunction "S_S") (pintype "passive"))
      (node (ref "R28") (pin "1") (pinfunction "1_1") (pintype "passive"))
    )
    (net (code "56") (name "Net-(Q1-PadB)") (class "Default")
      (node (ref "Q1") (pin "B") (pinfunction "B_B") (pintype "passive"))
      (node (ref "R23") (pin "1") (pinfunction "1_1") (pintype "passive"))
    )
    (net (code "57") (name "Net-(Q1-PadE)") (class "Default")
      (node (ref "Q1") (pin "E") (pinfunction "E_E") (pintype "passive"))
      (node (ref "R24") (pin "2") (pinfunction "2_2") (pintype "passive"))
      (node (ref "R25") (pin "2") (pinfunction "2_2") (pintype "passive"))
    )
    (net (code "58") (name "Net-(R16(ATTACK)-PadA)") (class "Default")
      (node (ref "R16(ATTACK)") (pin "A") (pinfunction "A_A") (pintype "passive"))
      (node (ref "R17") (pin "2") (pinfunction "2_2") (pintype "passive"))
    )
    (net (code "59") (name "Net-(R18(DECAY)-PadA)") (class "Default")
      (node (ref "R18(DECAY)") (pin "A") (pinfunction "A_A") (pintype "passive"))
      (node (ref "R19") (pin "2") (pinfunction "2_2") (pintype "passive"))
    )
    (net (code "60") (name "Net-(R20-Pad1)") (class "Default")
      (node (ref "R20") (pin "1") (pinfunction "1_1") (pintype "passive"))
      (node (ref "R21(BIAS)") (pin "A") (pinfunction "A_A") (pintype "passive"))
      (node (ref "R21(BIAS)") (pin "S") (pinfunction "S_S") (pintype "passive"))
    )
    (net (code "61") (name "Net-(R21-Pad1)") (class "Default")
      (node (ref "R21") (pin "1") (pinfunction "1_1") (pintype "passive"))
      (node (ref "SD_ATT") (pin "S") (pinfunction "S_S") (pintype "passive"))
    )
    (net (code "62") (name "Net-(R28(GAIN)-PadA)") (class "Default")
      (node (ref "R28(GAIN)") (pin "A") (pinfunction "A_A") (pintype "passive"))
      (node (ref "R29") (pin "1") (pinfunction "1_1") (pintype "passive"))
    )
    (net (code "63") (name "Net-(SIDE_CH_ONOFF-S)") (class "Default")
      (node (ref "SIDE_CHAI_TRIM") (pin "S") (pinfunction "S_S") (pintype "passive"))
      (node (ref "SIDE_CH_ONOFF") (pin "3") (pinfunction "S_3") (pintype "passive"))
    )
  )
)
